# Power.net
KiCad netlist of a schematic drawn in Altium Designer
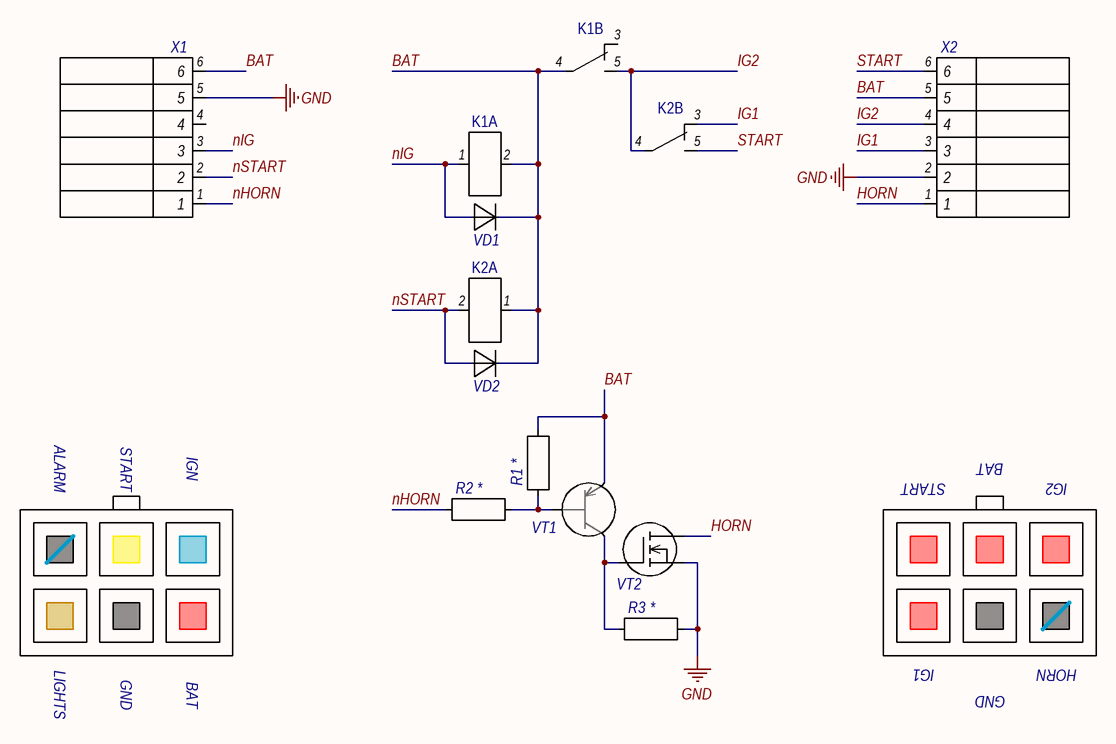
[diagram p0: Power.SchDoc]

(export (version "E")
  (design (tool "Eeschema 10.0.6"))
  (components
    (comp (ref "K1")
      (value "Relay, SPDT")
      (footprint "NRP07-C12D")
      (description "Реле, SPDT")
      (libsource (lib "el_mech") (part "Relay, SPDT"))
    )
    (comp (ref "K2")
      (value "Relay, SPDT")
      (footprint "NRP07-C12D")
      (description "Реле, SPDT")
      (libsource (lib "el_mech") (part "Relay, SPDT"))
    )
    (comp (ref "R1")
      (value "Резистор")
      (footprint "CHIP_0805_R")
      (fields (field (name "ALTIUM_VALUE") "*"))
      (libsource (lib "RCL") (part "Резистор"))
    )
    (comp (ref "R2")
      (value "Резистор")
      (footprint "CHIP_0805_R")
      (fields (field (name "ALTIUM_VALUE") "*"))
      (libsource (lib "RCL") (part "Резистор"))
    )
    (comp (ref "R3")
      (value "Резистор")
      (footprint "CHIP_0805_R")
      (fields (field (name "ALTIUM_VALUE") "*"))
      (libsource (lib "RCL") (part "Резистор"))
    )
    (comp (ref "VD1")
      (value "Diode, generic")
      (footprint "SMA")
      (libsource (lib "Semiconductors") (part "Diode, generic"))
    )
    (comp (ref "VD2")
      (value "Diode, generic")
      (footprint "SMA")
      (libsource (lib "Semiconductors") (part "Diode, generic"))
    )
    (comp (ref "VT1")
      (value "BJT, PNP")
      (footprint "SOT-23")
      (libsource (lib "Semiconductors") (part "BJT, PNP"))
    )
    (comp (ref "VT2")
      (value "MOSFET, N-ch")
      (footprint "TO-220")
      (libsource (lib "Semiconductors") (part "MOSFET, N-ch"))
    )
    (comp (ref "X1")
      (value "MF 2x03 M(R)")
      (footprint "MF 2x03 V")
      (description "MiniFit, 4.20mm 2x03")
      (libsource (lib "conn") (part "MF 2x03 M(R)"))
    )
    (comp (ref "X2")
      (value "MF 2x03 M(R)")
      (footprint "MF 2x03 R")
      (description "MiniFit, 4.20mm 2x03")
      (libsource (lib "conn") (part "MF 2x03 M(R)"))
    )
  )
  (nets
    (net (code "1") (name "/BAT") (class "Default")
      (node (ref "K1") (pin "2") (pinfunction "2_2") (pintype "passive"))
      (node (ref "K1") (pin "4") (pinfunction "4_4") (pintype "passive"))
      (node (ref "K2") (pin "1") (pinfunction "1_1") (pintype "passive"))
      (node (ref "R1") (pin "2") (pinfunction "2_2") (pintype "passive"))
      (node (ref "VD1") (pin "K") (pinfunction "2_K") (pintype "passive"))
      (node (ref "VD2") (pin "K") (pinfunction "2_K") (pintype "passive"))
      (node (ref "VT1") (pin "3") (pinfunction "3_3") (pintype "passive"))
      (node (ref "X1") (pin "6") (pinfunction "6_6") (pintype "passive"))
      (node (ref "X2") (pin "5") (pinfunction "5_5") (pintype "passive"))
    )
    (net (code "2") (name "/HORN") (class "Default")
      (node (ref "VT2") (pin "2") (pinfunction "2_2") (pintype "passive"))
      (node (ref "X2") (pin "1") (pinfunction "1_1") (pintype "passive"))
    )
    (net (code "3") (name "/IG1") (class "Default")
      (node (ref "K2") (pin "3") (pinfunction "3_3") (pintype "passive"))
      (node (ref "X2") (pin "3") (pinfunction "3_3") (pintype "passive"))
    )
    (net (code "4") (name "/IG2") (class "Default")
      (node (ref "K1") (pin "5") (pinfunction "5_5") (pintype "passive"))
      (node (ref "K2") (pin "4") (pinfunction "4_4") (pintype "passive"))
      (node (ref "X2") (pin "4") (pinfunction "4_4") (pintype "passive"))
    )
    (net (code "5") (name "/START") (class "Default")
      (node (ref "K2") (pin "5") (pinfunction "5_5") (pintype "passive"))
      (node (ref "X2") (pin "6") (pinfunction "6_6") (pintype "passive"))
    )
    (net (code "6") (name "/nHORN") (class "Default")
      (node (ref "R2") (pin "1") (pinfunction "1_1") (pintype "passive"))
      (node (ref "X1") (pin "1") (pinfunction "1_1") (pintype "passive"))
    )
    (net (code "7") (name "/nIG") (class "Default")
      (node (ref "K1") (pin "1") (pinfunction "1_1") (pintype "passive"))
      (node (ref "VD1") (pin "A") (pinfunction "1_A") (pintype "passive"))
      (node (ref "X1") (pin "3") (pinfunction "3_3") (pintype "passive"))
    )
    (net (code "8") (name "/nSTART") (class "Default")
      (node (ref "K2") (pin "2") (pinfunction "2_2") (pintype "passive"))
      (node (ref "VD2") (pin "A") (pinfunction "1_A") (pintype "passive"))
      (node (ref "X1") (pin "2") (pinfunction "2_2") (pintype "passive"))
    )
    (net (code "9") (name "GND") (class "Default")
      (node (ref "R3") (pin "2") (pinfunction "2_2") (pintype "passive"))
      (node (ref "VT2") (pin "3") (pinfunction "3_3") (pintype "passive"))
      (node (ref "X1") (pin "5") (pinfunction "5_5") (pintype "passive"))
      (node (ref "X2") (pin "2") (pinfunction "2_2") (pintype "passive"))
    )
    (net (code "10") (name "Net-(R1-Pad1)") (class "Default")
      (node (ref "R1") (pin "1") (pinfunction "1_1") (pintype "passive"))
      (node (ref "R2") (pin "2") (pinfunction "2_2") (pintype "passive"))
      (node (ref "VT1") (pin "1") (pinfunction "1_1") (pintype "passive"))
    )
    (net (code "11") (name "Net-(R3-Pad1)") (class "Default")
      (node (ref "R3") (pin "1") (pinfunction "1_1") (pintype "passive"))
      (node (ref "VT1") (pin "2") (pinfunction "2_2") (pintype "passive"))
      (node (ref "VT2") (pin "1") (pinfunction "1_1") (pintype "passive"))
    )
    (net (code "12") (name "unconnected-(K1-Pad3)") (class "Default")
      (node (ref "K1") (pin "3") (pinfunction "3_3") (pintype "passive"))
    )
    (net (code "13") (name "unconnected-(X1-Pad4)") (class "Default")
      (node (ref "X1") (pin "4") (pinfunction "4_4") (pintype "passive"))
    )
  )
)
